# Traction_Control_SMD.net
KiCad netlist of a schematic drawn in EAGLE
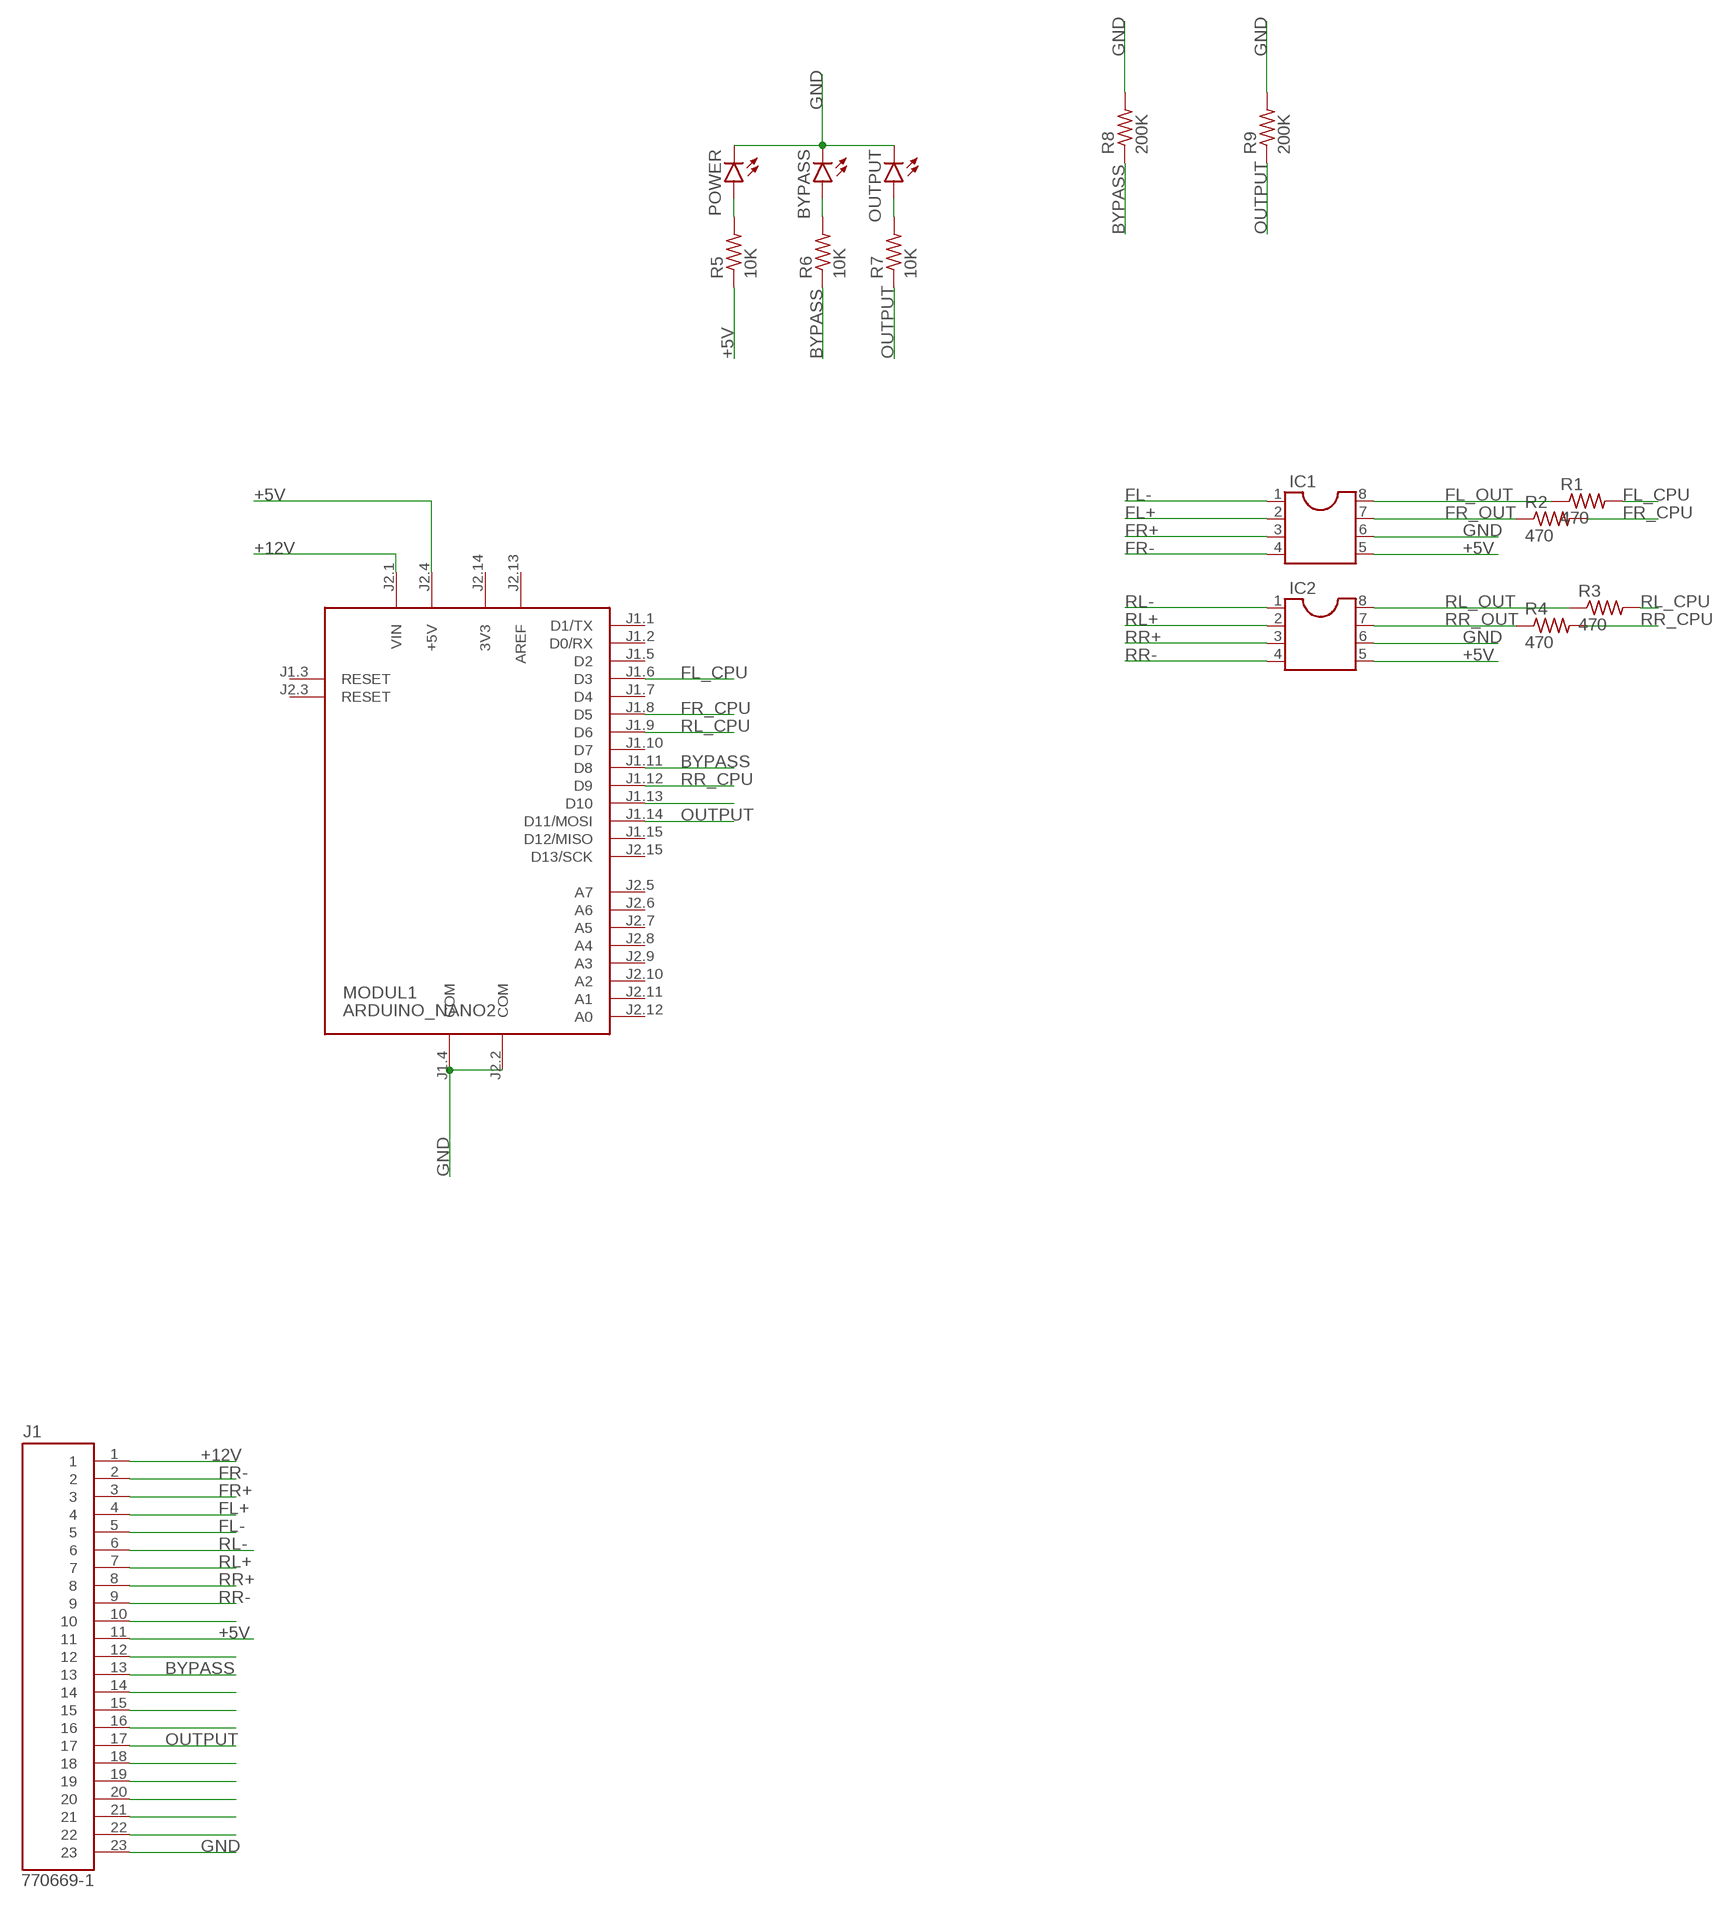
[diagram p0: schematic, sheet 1]

(export (version "E")
  (design (tool "Eeschema 10.0.6"))
  (components
    (comp (ref "BYPASS")
      (value "LEDCHIP-LED0805")
      (footprint "eagle-import:CHIP-LED0805")
      (libsource (lib "eagle-import") (part "LEDCHIP-LED0805"))
    )
    (comp (ref "IC1")
      (value "DIL8S")
      (footprint "eagle-import:SOCKET-08")
      (libsource (lib "eagle-import") (part "DIL8S"))
    )
    (comp (ref "IC2")
      (value "DIL8S")
      (footprint "eagle-import:SOCKET-08")
      (libsource (lib "eagle-import") (part "DIL8S"))
    )
    (comp (ref "J1")
      (value "770669-1")
      (footprint "eagle-import:TE_770669-1")
      (fields (field (name "MF") "TE Connectivity"))
      (libsource (lib "eagle-import") (part "770669-1"))
    )
    (comp (ref "MODUL1")
      (value "ARDUINO_NANO2")
      (footprint "eagle-import:ARDUINO_NANO2")
      (libsource (lib "eagle-import") (part "ARDUINO_NANO2"))
    )
    (comp (ref "OUTPUT")
      (value "LEDCHIP-LED0805")
      (footprint "eagle-import:CHIP-LED0805")
      (libsource (lib "eagle-import") (part "LEDCHIP-LED0805"))
    )
    (comp (ref "POWER")
      (value "LEDCHIP-LED0805")
      (footprint "eagle-import:CHIP-LED0805")
      (libsource (lib "eagle-import") (part "LEDCHIP-LED0805"))
    )
    (comp (ref "R1")
      (value "470")
      (footprint "eagle-import:R0805")
      (libsource (lib "eagle-import") (part "resistor_348_R-US_R0805"))
    )
    (comp (ref "R2")
      (value "470")
      (footprint "eagle-import:R0805")
      (libsource (lib "eagle-import") (part "resistor_348_R-US_R0805"))
    )
    (comp (ref "R3")
      (value "470")
      (footprint "eagle-import:R0805")
      (libsource (lib "eagle-import") (part "resistor_348_R-US_R0805"))
    )
    (comp (ref "R4")
      (value "470")
      (footprint "eagle-import:R0805")
      (libsource (lib "eagle-import") (part "resistor_348_R-US_R0805"))
    )
    (comp (ref "R5")
      (value "10K")
      (footprint "eagle-import:R0805")
      (libsource (lib "eagle-import") (part "R-US_R0805"))
    )
    (comp (ref "R6")
      (value "10K")
      (footprint "eagle-import:R0805")
      (libsource (lib "eagle-import") (part "R-US_R0805"))
    )
    (comp (ref "R7")
      (value "10K")
      (footprint "eagle-import:R0805")
      (libsource (lib "eagle-import") (part "R-US_R0805"))
    )
    (comp (ref "R8")
      (value "200K")
      (footprint "eagle-import:R0805")
      (libsource (lib "eagle-import") (part "R-US_R0805"))
    )
    (comp (ref "R9")
      (value "200K")
      (footprint "eagle-import:R0805")
      (libsource (lib "eagle-import") (part "R-US_R0805"))
    )
  )
  (nets
    (net (code "1") (name "/+5V") (class "Default")
      (node (ref "IC1") (pin "5") (pinfunction "5_5") (pintype "passive"))
      (node (ref "IC2") (pin "5") (pinfunction "5_5") (pintype "passive"))
      (node (ref "J1") (pin "11") (pinfunction "11_11") (pintype "passive"))
      (node (ref "MODUL1") (pin "J2.4") (pinfunction "+5V_J2.4") (pintype "power_in"))
      (node (ref "R5") (pin "1") (pinfunction "1_1") (pintype "passive"))
    )
    (net (code "2") (name "/+12V") (class "Default")
      (node (ref "J1") (pin "1") (pinfunction "1_1") (pintype "passive"))
      (node (ref "MODUL1") (pin "J2.1") (pinfunction "VIN_J2.1") (pintype "power_in"))
    )
    (net (code "3") (name "/3V3") (class "Default")
      (node (ref "MODUL1") (pin "J2.14") (pinfunction "3V3_J2.14") (pintype "power_in"))
    )
    (net (code "4") (name "/AREF") (class "Default")
      (node (ref "MODUL1") (pin "J2.13") (pinfunction "AREF_J2.13") (pintype "power_in"))
    )
    (net (code "5") (name "/BYPASS") (class "Default")
      (node (ref "J1") (pin "13") (pinfunction "13_13") (pintype "passive"))
      (node (ref "MODUL1") (pin "J1.11") (pinfunction "D8_J1.11") (pintype "bidirectional"))
      (node (ref "R6") (pin "1") (pinfunction "1_1") (pintype "passive"))
      (node (ref "R8") (pin "1") (pinfunction "1_1") (pintype "passive"))
    )
    (net (code "6") (name "/FL+") (class "Default")
      (node (ref "IC1") (pin "2") (pinfunction "2_2") (pintype "passive"))
      (node (ref "J1") (pin "4") (pinfunction "4_4") (pintype "passive"))
    )
    (net (code "7") (name "/FL-") (class "Default")
      (node (ref "IC1") (pin "1") (pinfunction "1_1") (pintype "passive"))
      (node (ref "J1") (pin "5") (pinfunction "5_5") (pintype "passive"))
    )
    (net (code "8") (name "/FL_CPU") (class "Default")
      (node (ref "MODUL1") (pin "J1.6") (pinfunction "D3_J1.6") (pintype "bidirectional"))
      (node (ref "R1") (pin "2") (pinfunction "2_2") (pintype "passive"))
    )
    (net (code "9") (name "/FL_OUT") (class "Default")
      (node (ref "IC1") (pin "8") (pinfunction "8_8") (pintype "passive"))
      (node (ref "R1") (pin "1") (pinfunction "1_1") (pintype "passive"))
    )
    (net (code "10") (name "/FR+") (class "Default")
      (node (ref "IC1") (pin "3") (pinfunction "3_3") (pintype "passive"))
      (node (ref "J1") (pin "3") (pinfunction "3_3") (pintype "passive"))
    )
    (net (code "11") (name "/FR-") (class "Default")
      (node (ref "IC1") (pin "4") (pinfunction "4_4") (pintype "passive"))
      (node (ref "J1") (pin "2") (pinfunction "2_2") (pintype "passive"))
    )
    (net (code "12") (name "/FR_CPU") (class "Default")
      (node (ref "MODUL1") (pin "J1.8") (pinfunction "D5_J1.8") (pintype "bidirectional"))
      (node (ref "R2") (pin "2") (pinfunction "2_2") (pintype "passive"))
    )
    (net (code "13") (name "/FR_OUT") (class "Default")
      (node (ref "IC1") (pin "7") (pinfunction "7_7") (pintype "passive"))
      (node (ref "R2") (pin "1") (pinfunction "1_1") (pintype "passive"))
    )
    (net (code "14") (name "/GND") (class "Default")
      (node (ref "BYPASS") (pin "C") (pinfunction "C_C") (pintype "passive"))
      (node (ref "IC1") (pin "6") (pinfunction "6_6") (pintype "passive"))
      (node (ref "IC2") (pin "6") (pinfunction "6_6") (pintype "passive"))
      (node (ref "J1") (pin "23") (pinfunction "23_23") (pintype "passive"))
      (node (ref "MODUL1") (pin "J1.4") (pinfunction "COM_J1.4") (pintype "power_in"))
      (node (ref "MODUL1") (pin "J2.2") (pinfunction "COM_J2.2") (pintype "power_in"))
      (node (ref "OUTPUT") (pin "C") (pinfunction "C_C") (pintype "passive"))
      (node (ref "POWER") (pin "C") (pinfunction "C_C") (pintype "passive"))
      (node (ref "R8") (pin "2") (pinfunction "2_2") (pintype "passive"))
      (node (ref "R9") (pin "2") (pinfunction "2_2") (pintype "passive"))
    )
    (net (code "15") (name "/OUTPUT") (class "Default")
      (node (ref "J1") (pin "17") (pinfunction "17_17") (pintype "passive"))
      (node (ref "MODUL1") (pin "J1.14") (pinfunction "D11/MOSI_J1.14") (pintype "bidirectional"))
      (node (ref "R7") (pin "1") (pinfunction "1_1") (pintype "passive"))
      (node (ref "R9") (pin "1") (pinfunction "1_1") (pintype "passive"))
    )
    (net (code "16") (name "/RL+") (class "Default")
      (node (ref "IC2") (pin "2") (pinfunction "2_2") (pintype "passive"))
      (node (ref "J1") (pin "7") (pinfunction "7_7") (pintype "passive"))
    )
    (net (code "17") (name "/RL-") (class "Default")
      (node (ref "IC2") (pin "1") (pinfunction "1_1") (pintype "passive"))
      (node (ref "J1") (pin "6") (pinfunction "6_6") (pintype "passive"))
    )
    (net (code "18") (name "/RL_CPU") (class "Default")
      (node (ref "MODUL1") (pin "J1.9") (pinfunction "D6_J1.9") (pintype "bidirectional"))
      (node (ref "R3") (pin "2") (pinfunction "2_2") (pintype "passive"))
    )
    (net (code "19") (name "/RL_OUT") (class "Default")
      (node (ref "IC2") (pin "8") (pinfunction "8_8") (pintype "passive"))
      (node (ref "R3") (pin "1") (pinfunction "1_1") (pintype "passive"))
    )
    (net (code "20") (name "/RR+") (class "Default")
      (node (ref "IC2") (pin "3") (pinfunction "3_3") (pintype "passive"))
      (node (ref "J1") (pin "8") (pinfunction "8_8") (pintype "passive"))
    )
    (net (code "21") (name "/RR-") (class "Default")
      (node (ref "IC2") (pin "4") (pinfunction "4_4") (pintype "passive"))
      (node (ref "J1") (pin "9") (pinfunction "9_9") (pintype "passive"))
    )
    (net (code "22") (name "/RR_CPU") (class "Default")
      (node (ref "MODUL1") (pin "J1.12") (pinfunction "D9_J1.12") (pintype "bidirectional"))
      (node (ref "R4") (pin "2") (pinfunction "2_2") (pintype "passive"))
    )
    (net (code "23") (name "/RR_OUT") (class "Default")
      (node (ref "IC2") (pin "7") (pinfunction "7_7") (pintype "passive"))
      (node (ref "R4") (pin "1") (pinfunction "1_1") (pintype "passive"))
    )
    (net (code "24") (name "Net-(BYPASS-PadA)") (class "Default")
      (node (ref "BYPASS") (pin "A") (pinfunction "A_A") (pintype "passive"))
      (node (ref "R6") (pin "2") (pinfunction "2_2") (pintype "passive"))
    )
    (net (code "25") (name "Net-(OUTPUT-PadA)") (class "Default")
      (node (ref "OUTPUT") (pin "A") (pinfunction "A_A") (pintype "passive"))
      (node (ref "R7") (pin "2") (pinfunction "2_2") (pintype "passive"))
    )
    (net (code "26") (name "Net-(POWER-PadA)") (class "Default")
      (node (ref "POWER") (pin "A") (pinfunction "A_A") (pintype "passive"))
      (node (ref "R5") (pin "2") (pinfunction "2_2") (pintype "passive"))
    )
    (net (code "27") (name "unconnected-(J1-Pad10)") (class "Default")
      (node (ref "J1") (pin "10") (pinfunction "10_10") (pintype "passive"))
    )
    (net (code "28") (name "unconnected-(J1-Pad12)") (class "Default")
      (node (ref "J1") (pin "12") (pinfunction "12_12") (pintype "passive"))
    )
    (net (code "29") (name "unconnected-(J1-Pad14)") (class "Default")
      (node (ref "J1") (pin "14") (pinfunction "14_14") (pintype "passive"))
    )
    (net (code "30") (name "unconnected-(J1-Pad15)") (class "Default")
      (node (ref "J1") (pin "15") (pinfunction "15_15") (pintype "passive"))
    )
    (net (code "31") (name "unconnected-(J1-Pad16)") (class "Default")
      (node (ref "J1") (pin "16") (pinfunction "16_16") (pintype "passive"))
    )
    (net (code "32") (name "unconnected-(J1-Pad18)") (class "Default")
      (node (ref "J1") (pin "18") (pinfunction "18_18") (pintype "passive"))
    )
    (net (code "33") (name "unconnected-(J1-Pad19)") (class "Default")
      (node (ref "J1") (pin "19") (pinfunction "19_19") (pintype "passive"))
    )
    (net (code "34") (name "unconnected-(J1-Pad20)") (class "Default")
      (node (ref "J1") (pin "20") (pinfunction "20_20") (pintype "passive"))
    )
    (net (code "35") (name "unconnected-(J1-Pad21)") (class "Default")
      (node (ref "J1") (pin "21") (pinfunction "21_21") (pintype "passive"))
    )
    (net (code "36") (name "unconnected-(J1-Pad22)") (class "Default")
      (node (ref "J1") (pin "22") (pinfunction "22_22") (pintype "passive"))
    )
    (net (code "37") (name "unconnected-(MODUL1-A0-PadJ2.12)") (class "Default")
      (node (ref "MODUL1") (pin "J2.12") (pinfunction "A0_J2.12") (pintype "bidirectional"))
    )
    (net (code "38") (name "unconnected-(MODUL1-A1-PadJ2.11)") (class "Default")
      (node (ref "MODUL1") (pin "J2.11") (pinfunction "A1_J2.11") (pintype "bidirectional"))
    )
    (net (code "39") (name "unconnected-(MODUL1-A2-PadJ2.10)") (class "Default")
      (node (ref "MODUL1") (pin "J2.10") (pinfunction "A2_J2.10") (pintype "bidirectional"))
    )
    (net (code "40") (name "unconnected-(MODUL1-A3-PadJ2.9)") (class "Default")
      (node (ref "MODUL1") (pin "J2.9") (pinfunction "A3_J2.9") (pintype "bidirectional"))
    )
    (net (code "41") (name "unconnected-(MODUL1-A4-PadJ2.8)") (class "Default")
      (node (ref "MODUL1") (pin "J2.8") (pinfunction "A4_J2.8") (pintype "bidirectional"))
    )
    (net (code "42") (name "unconnected-(MODUL1-A5-PadJ2.7)") (class "Default")
      (node (ref "MODUL1") (pin "J2.7") (pinfunction "A5_J2.7") (pintype "bidirectional"))
    )
    (net (code "43") (name "unconnected-(MODUL1-A6-PadJ2.6)") (class "Default")
      (node (ref "MODUL1") (pin "J2.6") (pinfunction "A6_J2.6") (pintype "bidirectional"))
    )
    (net (code "44") (name "unconnected-(MODUL1-A7-PadJ2.5)") (class "Default")
      (node (ref "MODUL1") (pin "J2.5") (pinfunction "A7_J2.5") (pintype "bidirectional"))
    )
    (net (code "45") (name "unconnected-(MODUL1-D0{slash}RX-PadJ1.2)") (class "Default")
      (node (ref "MODUL1") (pin "J1.2") (pinfunction "D0/RX_J1.2") (pintype "bidirectional"))
    )
    (net (code "46") (name "unconnected-(MODUL1-D1{slash}TX-PadJ1.1)") (class "Default")
      (node (ref "MODUL1") (pin "J1.1") (pinfunction "D1/TX_J1.1") (pintype "bidirectional"))
    )
    (net (code "47") (name "unconnected-(MODUL1-D2-PadJ1.5)") (class "Default")
      (node (ref "MODUL1") (pin "J1.5") (pinfunction "D2_J1.5") (pintype "bidirectional"))
    )
    (net (code "48") (name "unconnected-(MODUL1-D4-PadJ1.7)") (class "Default")
      (node (ref "MODUL1") (pin "J1.7") (pinfunction "D4_J1.7") (pintype "bidirectional"))
    )
    (net (code "49") (name "unconnected-(MODUL1-D7-PadJ1.10)") (class "Default")
      (node (ref "MODUL1") (pin "J1.10") (pinfunction "D7_J1.10") (pintype "bidirectional"))
    )
    (net (code "50") (name "unconnected-(MODUL1-D10-PadJ1.13)") (class "Default")
      (node (ref "MODUL1") (pin "J1.13") (pinfunction "D10_J1.13") (pintype "bidirectional"))
    )
    (net (code "51") (name "unconnected-(MODUL1-D12{slash}MISO-PadJ1.15)") (class "Default")
      (node (ref "MODUL1") (pin "J1.15") (pinfunction "D12/MISO_J1.15") (pintype "bidirectional"))
    )
    (net (code "52") (name "unconnected-(MODUL1-D13{slash}SCK-PadJ2.15)") (class "Default")
      (node (ref "MODUL1") (pin "J2.15") (pinfunction "D13/SCK_J2.15") (pintype "bidirectional"))
    )
    (net (code "53") (name "unconnected-(MODUL1-RESET-PadJ1.3)") (class "Default")
      (node (ref "MODUL1") (pin "J1.3") (pinfunction "RESET_J1.3") (pintype "bidirectional"))
    )
    (net (code "54") (name "unconnected-(MODUL1-RESET-PadJ2.3)") (class "Default")
      (node (ref "MODUL1") (pin "J2.3") (pinfunction "RESET_J2.3") (pintype "bidirectional"))
    )
  )
)
